# SensorModule.net
KiCad netlist of a schematic drawn in EAGLE
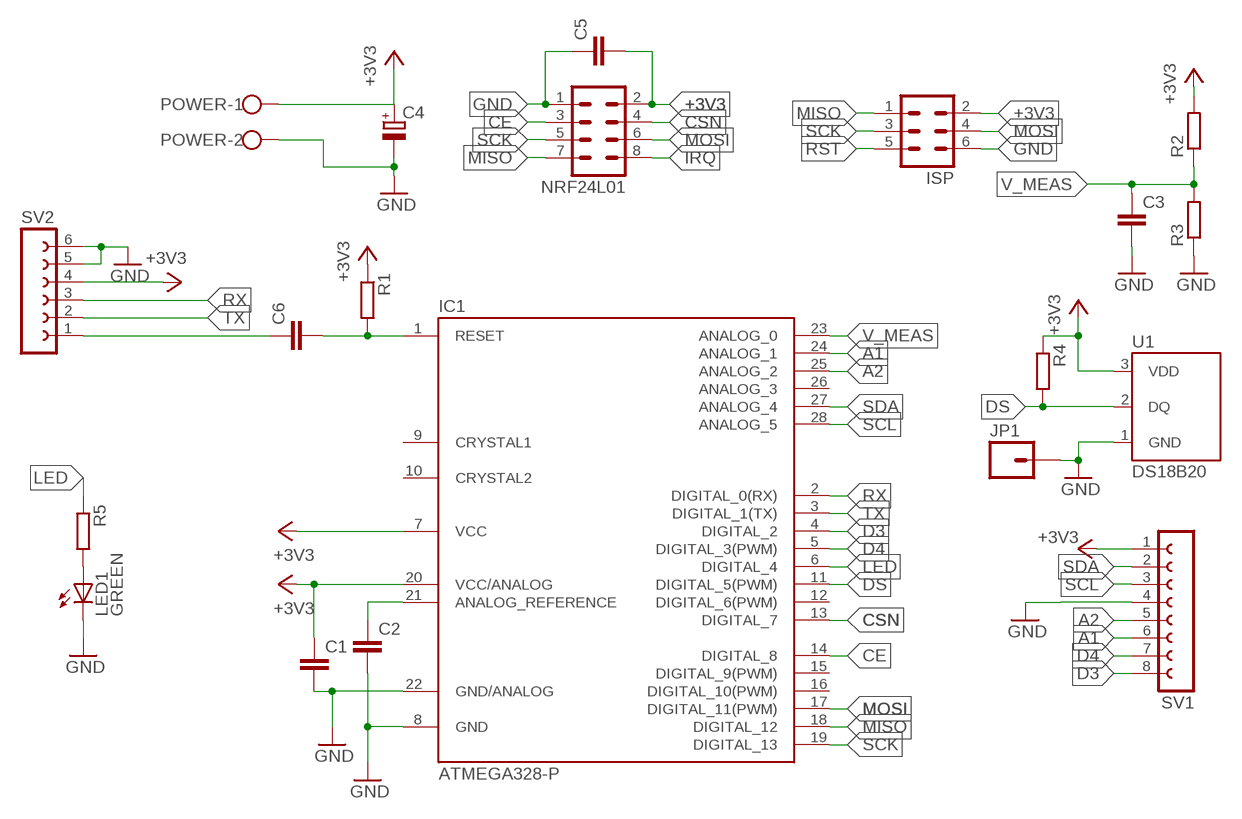
[diagram p0: schematic, sheet 1]

(export (version "E")
  (design (tool "Eeschema 10.0.6"))
  (components
    (comp (ref "C1")
      (value "C-EU025-025X050")
      (footprint "eagle-import:C025-025X050")
      (libsource (lib "eagle-import") (part "C-EU025-025X050"))
    )
    (comp (ref "C2")
      (value "C-EU025-025X050")
      (footprint "eagle-import:C025-025X050")
      (libsource (lib "eagle-import") (part "C-EU025-025X050"))
    )
    (comp (ref "C3")
      (value "C-EU025-025X050")
      (footprint "eagle-import:C025-025X050")
      (libsource (lib "eagle-import") (part "C-EU025-025X050"))
    )
    (comp (ref "C4")
      (value "CPOL-EUE2.5-5")
      (footprint "eagle-import:E2,5-5")
      (libsource (lib "eagle-import") (part "CPOL-EUE2.5-5"))
    )
    (comp (ref "C5")
      (value "C-EU025-025X050")
      (footprint "eagle-import:C025-025X050")
      (libsource (lib "eagle-import") (part "C-EU025-025X050"))
    )
    (comp (ref "C6")
      (value "C-EU025-025X050")
      (footprint "eagle-import:C025-025X050")
      (libsource (lib "eagle-import") (part "C-EU025-025X050"))
    )
    (comp (ref "IC1")
      (value "ATMEGA328-P")
      (footprint "eagle-import:DIL28-3")
      (libsource (lib "eagle-import") (part "ATMEGA168-PU"))
    )
    (comp (ref "ISP")
      (value "MA03-2")
      (footprint "eagle-import:MA03-2")
      (libsource (lib "eagle-import") (part "MA03-2"))
    )
    (comp (ref "JP1")
      (value "M01PTH_LONGPAD")
      (footprint "eagle-import:1X01_LONGPAD")
      (libsource (lib "eagle-import") (part "M01PTH_LONGPAD"))
    )
    (comp (ref "LED1")
      (value "GREEN")
      (footprint "eagle-import:LED5MM")
      (libsource (lib "eagle-import") (part "LED5MM"))
    )
    (comp (ref "NRF24L01")
      (value "MA04-2")
      (footprint "eagle-import:MA04-2")
      (libsource (lib "eagle-import") (part "MA04-2"))
    )
    (comp (ref "POWER")
      (value "W237-102")
      (footprint "eagle-import:W237-102")
      (fields (field (name "MPN") "237-102"))
      (libsource (lib "eagle-import") (part "W237-102"))
    )
    (comp (ref "R1")
      (value "R-EU_0204/2V")
      (footprint "eagle-import:0204V")
      (libsource (lib "eagle-import") (part "R-EU_0204/2V"))
    )
    (comp (ref "R2")
      (value "R-EU_0204/2V")
      (footprint "eagle-import:0204V")
      (libsource (lib "eagle-import") (part "R-EU_0204/2V"))
    )
    (comp (ref "R3")
      (value "R-EU_0204/2V")
      (footprint "eagle-import:0204V")
      (libsource (lib "eagle-import") (part "R-EU_0204/2V"))
    )
    (comp (ref "R4")
      (value "R-EU_0204/2V")
      (footprint "eagle-import:0204V")
      (libsource (lib "eagle-import") (part "R-EU_0204/2V"))
    )
    (comp (ref "R5")
      (value "R-EU_0204/2V")
      (footprint "eagle-import:0204V")
      (libsource (lib "eagle-import") (part "R-EU_0204/2V"))
    )
    (comp (ref "SV1")
      (value "FE08-1")
      (footprint "eagle-import:FE08")
      (libsource (lib "eagle-import") (part "FE08-1"))
    )
    (comp (ref "SV2")
      (value "FE06-1")
      (footprint "eagle-import:FE06")
      (libsource (lib "eagle-import") (part "FE06-1"))
    )
    (comp (ref "U1")
      (value "DS18B20")
      (footprint "eagle-import:TO-92-AMMO")
      (libsource (lib "eagle-import") (part "DS18B20"))
    )
  )
  (nets
    (net (code "1") (name "+3V3") (class "Default")
      (node (ref "C1") (pin "1") (pinfunction "1_1") (pintype "passive"))
      (node (ref "C4") (pin "+") (pinfunction "+_+") (pintype "passive"))
      (node (ref "C5") (pin "2") (pinfunction "2_2") (pintype "passive"))
      (node (ref "IC1") (pin "20") (pinfunction "VCC/ANALOG_20") (pintype "passive"))
      (node (ref "IC1") (pin "7") (pinfunction "VCC_7") (pintype "power_in"))
      (node (ref "ISP") (pin "2") (pinfunction "2_2") (pintype "passive"))
      (node (ref "NRF24L01") (pin "2") (pinfunction "2_2") (pintype "passive"))
      (node (ref "POWER") (pin "1") (pinfunction "KL_1") (pintype "passive"))
      (node (ref "R1") (pin "1") (pinfunction "1_1") (pintype "passive"))
      (node (ref "R2") (pin "2") (pinfunction "2_2") (pintype "passive"))
      (node (ref "R4") (pin "1") (pinfunction "1_1") (pintype "passive"))
      (node (ref "SV1") (pin "1") (pinfunction "1_1") (pintype "passive"))
      (node (ref "SV2") (pin "4") (pinfunction "4_4") (pintype "passive"))
      (node (ref "U1") (pin "3") (pinfunction "VDD_3") (pintype "power_in"))
    )
    (net (code "2") (name "A1") (class "Default")
      (node (ref "IC1") (pin "24") (pinfunction "ANALOG_1_24") (pintype "bidirectional"))
      (node (ref "SV1") (pin "6") (pinfunction "6_6") (pintype "passive"))
    )
    (net (code "3") (name "A2") (class "Default")
      (node (ref "IC1") (pin "25") (pinfunction "ANALOG_2_25") (pintype "bidirectional"))
      (node (ref "SV1") (pin "5") (pinfunction "5_5") (pintype "passive"))
    )
    (net (code "4") (name "CE") (class "Default")
      (node (ref "IC1") (pin "14") (pinfunction "DIGITAL_8_14") (pintype "bidirectional"))
      (node (ref "NRF24L01") (pin "3") (pinfunction "3_3") (pintype "passive"))
    )
    (net (code "5") (name "CSN") (class "Default")
      (node (ref "IC1") (pin "13") (pinfunction "DIGITAL_7_13") (pintype "bidirectional"))
      (node (ref "NRF24L01") (pin "4") (pinfunction "4_4") (pintype "passive"))
    )
    (net (code "6") (name "D3") (class "Default")
      (node (ref "IC1") (pin "4") (pinfunction "DIGITAL_2_4") (pintype "bidirectional"))
      (node (ref "SV1") (pin "8") (pinfunction "8_8") (pintype "passive"))
    )
    (net (code "7") (name "D4") (class "Default")
      (node (ref "IC1") (pin "5") (pinfunction "DIGITAL_3(PWM)_5") (pintype "bidirectional"))
      (node (ref "SV1") (pin "7") (pinfunction "7_7") (pintype "passive"))
    )
    (net (code "8") (name "DS") (class "Default")
      (node (ref "IC1") (pin "11") (pinfunction "DIGITAL_5(PWM)_11") (pintype "bidirectional"))
      (node (ref "R4") (pin "2") (pinfunction "2_2") (pintype "passive"))
      (node (ref "U1") (pin "2") (pinfunction "DQ_2") (pintype "bidirectional"))
    )
    (net (code "9") (name "GND") (class "Default")
      (node (ref "C1") (pin "2") (pinfunction "2_2") (pintype "passive"))
      (node (ref "C2") (pin "2") (pinfunction "2_2") (pintype "passive"))
      (node (ref "C3") (pin "2") (pinfunction "2_2") (pintype "passive"))
      (node (ref "C4") (pin "-") (pinfunction "-_-") (pintype "passive"))
      (node (ref "C5") (pin "1") (pinfunction "1_1") (pintype "passive"))
      (node (ref "IC1") (pin "22") (pinfunction "GND/ANALOG_22") (pintype "power_in"))
      (node (ref "IC1") (pin "8") (pinfunction "GND_8") (pintype "power_in"))
      (node (ref "ISP") (pin "6") (pinfunction "6_6") (pintype "passive"))
      (node (ref "JP1") (pin "1") (pinfunction "1_1") (pintype "passive"))
      (node (ref "LED1") (pin "K") (pinfunction "C_K") (pintype "passive"))
      (node (ref "NRF24L01") (pin "1") (pinfunction "1_1") (pintype "passive"))
      (node (ref "POWER") (pin "2") (pinfunction "KL_2") (pintype "passive"))
      (node (ref "R3") (pin "1") (pinfunction "1_1") (pintype "passive"))
      (node (ref "SV1") (pin "4") (pinfunction "4_4") (pintype "passive"))
      (node (ref "SV2") (pin "5") (pinfunction "5_5") (pintype "passive"))
      (node (ref "SV2") (pin "6") (pinfunction "6_6") (pintype "passive"))
      (node (ref "U1") (pin "1") (pinfunction "GND_1") (pintype "power_in"))
    )
    (net (code "10") (name "IRQ") (class "Default")
      (node (ref "NRF24L01") (pin "8") (pinfunction "8_8") (pintype "passive"))
    )
    (net (code "11") (name "LED") (class "Default")
      (node (ref "IC1") (pin "6") (pinfunction "DIGITAL_4_6") (pintype "bidirectional"))
      (node (ref "R5") (pin "1") (pinfunction "1_1") (pintype "passive"))
    )
    (net (code "12") (name "MISO") (class "Default")
      (node (ref "IC1") (pin "18") (pinfunction "DIGITAL_12_18") (pintype "bidirectional"))
      (node (ref "ISP") (pin "1") (pinfunction "1_1") (pintype "passive"))
      (node (ref "NRF24L01") (pin "7") (pinfunction "7_7") (pintype "passive"))
    )
    (net (code "13") (name "MOSI") (class "Default")
      (node (ref "IC1") (pin "17") (pinfunction "DIGITAL_11(PWM)_17") (pintype "bidirectional"))
      (node (ref "ISP") (pin "4") (pinfunction "4_4") (pintype "passive"))
      (node (ref "NRF24L01") (pin "6") (pinfunction "6_6") (pintype "passive"))
    )
    (net (code "14") (name "Net-(C6-Pad1)") (class "Default")
      (node (ref "C6") (pin "1") (pinfunction "1_1") (pintype "passive"))
      (node (ref "SV2") (pin "1") (pinfunction "1_1") (pintype "passive"))
    )
    (net (code "15") (name "Net-(IC1-ANALOG_REFERENCE)") (class "Default")
      (node (ref "C2") (pin "1") (pinfunction "1_1") (pintype "passive"))
      (node (ref "IC1") (pin "21") (pinfunction "ANALOG_REFERENCE_21") (pintype "passive"))
    )
    (net (code "16") (name "Net-(IC1-RESET)") (class "Default")
      (node (ref "C6") (pin "2") (pinfunction "2_2") (pintype "passive"))
      (node (ref "IC1") (pin "1") (pinfunction "RESET_1") (pintype "bidirectional"))
      (node (ref "R1") (pin "2") (pinfunction "2_2") (pintype "passive"))
    )
    (net (code "17") (name "Net-(LED1-PadA)") (class "Default")
      (node (ref "LED1") (pin "A") (pinfunction "A_A") (pintype "passive"))
      (node (ref "R5") (pin "2") (pinfunction "2_2") (pintype "passive"))
    )
    (net (code "18") (name "RST") (class "Default")
      (node (ref "ISP") (pin "5") (pinfunction "5_5") (pintype "passive"))
    )
    (net (code "19") (name "RX") (class "Default")
      (node (ref "IC1") (pin "2") (pinfunction "DIGITAL_0(RX)_2") (pintype "bidirectional"))
      (node (ref "SV2") (pin "3") (pinfunction "3_3") (pintype "passive"))
    )
    (net (code "20") (name "SCK") (class "Default")
      (node (ref "IC1") (pin "19") (pinfunction "DIGITAL_13_19") (pintype "bidirectional"))
      (node (ref "ISP") (pin "3") (pinfunction "3_3") (pintype "passive"))
      (node (ref "NRF24L01") (pin "5") (pinfunction "5_5") (pintype "passive"))
    )
    (net (code "21") (name "SCL") (class "Default")
      (node (ref "IC1") (pin "28") (pinfunction "ANALOG_5_28") (pintype "bidirectional"))
      (node (ref "SV1") (pin "3") (pinfunction "3_3") (pintype "passive"))
    )
    (net (code "22") (name "SDA") (class "Default")
      (node (ref "IC1") (pin "27") (pinfunction "ANALOG_4_27") (pintype "bidirectional"))
      (node (ref "SV1") (pin "2") (pinfunction "2_2") (pintype "passive"))
    )
    (net (code "23") (name "TX") (class "Default")
      (node (ref "IC1") (pin "3") (pinfunction "DIGITAL_1(TX)_3") (pintype "bidirectional"))
      (node (ref "SV2") (pin "2") (pinfunction "2_2") (pintype "passive"))
    )
    (net (code "24") (name "V_MEAS") (class "Default")
      (node (ref "C3") (pin "1") (pinfunction "1_1") (pintype "passive"))
      (node (ref "IC1") (pin "23") (pinfunction "ANALOG_0_23") (pintype "bidirectional"))
      (node (ref "R2") (pin "1") (pinfunction "1_1") (pintype "passive"))
      (node (ref "R3") (pin "2") (pinfunction "2_2") (pintype "passive"))
    )
    (net (code "25") (name "unconnected-(IC1-ANALOG_3-Pad26)") (class "Default")
      (node (ref "IC1") (pin "26") (pinfunction "ANALOG_3_26") (pintype "bidirectional"))
    )
    (net (code "26") (name "unconnected-(IC1-CRYSTAL1-Pad9)") (class "Default")
      (node (ref "IC1") (pin "9") (pinfunction "CRYSTAL1_9") (pintype "bidirectional"))
    )
    (net (code "27") (name "unconnected-(IC1-CRYSTAL2-Pad10)") (class "Default")
      (node (ref "IC1") (pin "10") (pinfunction "CRYSTAL2_10") (pintype "bidirectional"))
    )
    (net (code "28") (name "unconnected-(IC1-DIGITAL_6(PWM)-Pad12)") (class "Default")
      (node (ref "IC1") (pin "12") (pinfunction "DIGITAL_6(PWM)_12") (pintype "bidirectional"))
    )
    (net (code "29") (name "unconnected-(IC1-DIGITAL_9(PWM)-Pad15)") (class "Default")
      (node (ref "IC1") (pin "15") (pinfunction "DIGITAL_9(PWM)_15") (pintype "bidirectional"))
    )
    (net (code "30") (name "unconnected-(IC1-DIGITAL_10(PWM)-Pad16)") (class "Default")
      (node (ref "IC1") (pin "16") (pinfunction "DIGITAL_10(PWM)_16") (pintype "bidirectional"))
    )
  )
)
